# Synchronous_Rectification_Stage.net
KiCad netlist of a schematic drawn in Altium Designer
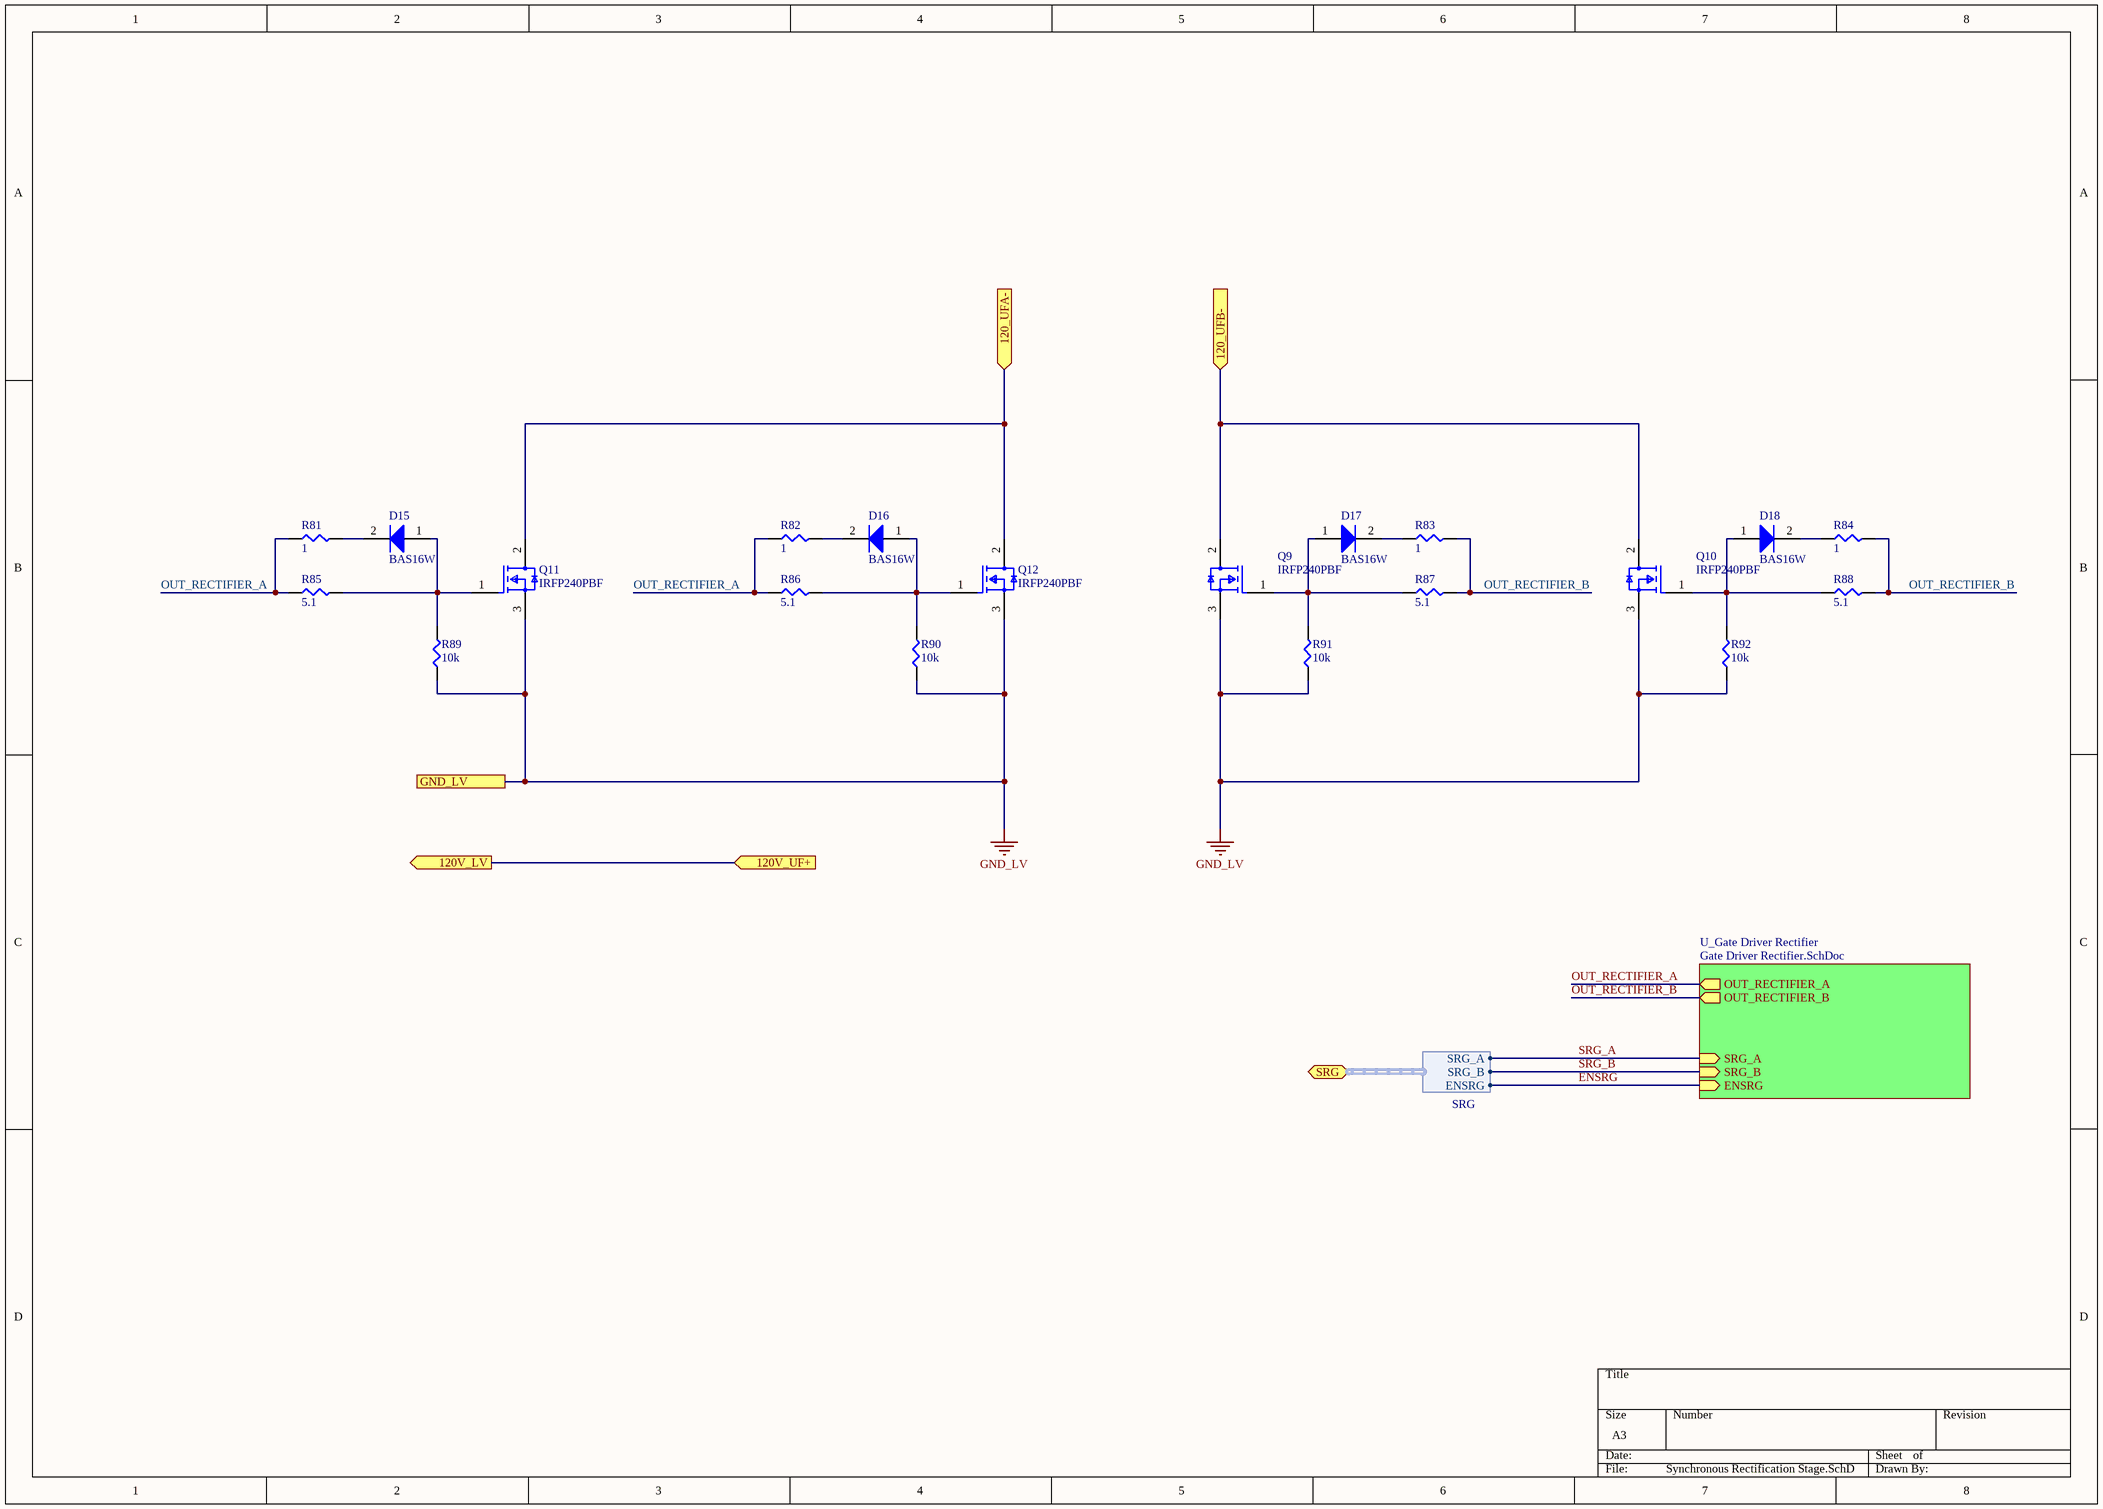
[diagram p0: Synchronous Rectification Stage.SchDoc]

(export (version "E")
  (design (tool "Eeschema 10.0.6"))
  (components
    (comp (ref "D15")
      (value "BAS16W")
      (footprint "SODFL250X110-2N")
      (description "Silicon Switching Diode, SOT323, Reel, Green")
      (fields (field (name "MANUFACTURER") "Infineon"))
      (libsource (lib "PFC_Stage") (part "BAS16_SOD"))
    )
    (comp (ref "D16")
      (value "BAS16W")
      (footprint "SODFL250X110-2N")
      (description "Silicon Switching Diode, SOT323, Reel, Green")
      (fields (field (name "MANUFACTURER") "Infineon"))
      (libsource (lib "PFC_Stage") (part "BAS16_SOD"))
    )
    (comp (ref "D17")
      (value "BAS16W")
      (footprint "SODFL250X110-2N")
      (description "Silicon Switching Diode, SOT323, Reel, Green")
      (fields (field (name "MANUFACTURER") "Infineon"))
      (libsource (lib "PFC_Stage") (part "BAS16_SOD"))
    )
    (comp (ref "D18")
      (value "BAS16W")
      (footprint "SODFL250X110-2N")
      (description "Silicon Switching Diode, SOT323, Reel, Green")
      (fields (field (name "MANUFACTURER") "Infineon"))
      (libsource (lib "PFC_Stage") (part "BAS16_SOD"))
    )
    (comp (ref "Q9")
      (value "IRFP240PBF")
      (footprint "FP-E19-0614-MFG")
      (description "MOSFET N-CH 200V 20A TO-247AC")
      (fields
        (field (name "MANUFACTURER") "Vishay")
        (field (name "OCTOPART") "https://octopart.com/irfp240pbf-vishay-46527395")
      )
      (libsource (lib "Altium Content Vault") (part "277670f45256a45703965f138927d09"))
    )
    (comp (ref "Q10")
      (value "IRFP240PBF")
      (footprint "FP-E19-0614-MFG")
      (description "MOSFET N-CH 200V 20A TO-247AC")
      (fields
        (field (name "MANUFACTURER") "Vishay")
        (field (name "OCTOPART") "https://octopart.com/irfp240pbf-vishay-46527395")
      )
      (libsource (lib "Altium Content Vault") (part "277670f45256a45703965f138927d09"))
    )
    (comp (ref "Q11")
      (value "IRFP240PBF")
      (footprint "FP-E19-0614-MFG")
      (description "MOSFET N-CH 200V 20A TO-247AC")
      (fields
        (field (name "MANUFACTURER") "Vishay")
        (field (name "OCTOPART") "https://octopart.com/irfp240pbf-vishay-46527395")
      )
      (libsource (lib "Altium Content Vault") (part "277670f45256a45703965f138927d09"))
    )
    (comp (ref "Q12")
      (value "IRFP240PBF")
      (footprint "FP-E19-0614-MFG")
      (description "MOSFET N-CH 200V 20A TO-247AC")
      (fields
        (field (name "MANUFACTURER") "Vishay")
        (field (name "OCTOPART") "https://octopart.com/irfp240pbf-vishay-46527395")
      )
      (libsource (lib "Altium Content Vault") (part "277670f45256a45703965f138927d09"))
    )
    (comp (ref "R81")
      (value "1")
      (footprint "SMD-0805-RES")
      (description "RES SMD 1 OHM 1% 1/3W 0805")
      (fields (field (name "PART NUMBER") "ERJ-6BQF1R0V") (field (name "DIGI-KEY PART NUMBER") "P17499CT-ND"))
      (libsource (lib "Panasonic_ERJ_0805") (part "ERJ-6BQF1R0V"))
    )
    (comp (ref "R82")
      (value "1")
      (footprint "SMD-0805-RES")
      (description "RES SMD 1 OHM 1% 1/3W 0805")
      (fields (field (name "PART NUMBER") "ERJ-6BQF1R0V") (field (name "DIGI-KEY PART NUMBER") "P17499CT-ND"))
      (libsource (lib "Panasonic_ERJ_0805") (part "ERJ-6BQF1R0V"))
    )
    (comp (ref "R83")
      (value "1")
      (footprint "SMD-0805-RES")
      (description "RES SMD 1 OHM 1% 1/3W 0805")
      (fields (field (name "PART NUMBER") "ERJ-6BQF1R0V") (field (name "DIGI-KEY PART NUMBER") "P17499CT-ND"))
      (libsource (lib "Panasonic_ERJ_0805") (part "ERJ-6BQF1R0V"))
    )
    (comp (ref "R84")
      (value "1")
      (footprint "SMD-0805-RES")
      (description "RES SMD 1 OHM 1% 1/3W 0805")
      (fields (field (name "PART NUMBER") "ERJ-6BQF1R0V") (field (name "DIGI-KEY PART NUMBER") "P17499CT-ND"))
      (libsource (lib "Panasonic_ERJ_0805") (part "ERJ-6BQF1R0V"))
    )
    (comp (ref "R85")
      (value "5.1")
      (footprint "SMD-1206-RES")
      (description "RES SMD 5.1 OHM 1% 1/2W 1206")
      (fields (field (name "PART NUMBER") "ERJ-8BQF5R1V") (field (name "DIGI-KEY PART NUMBER") "P17617CT-ND"))
      (libsource (lib "Panasonic_ERJ_1206") (part "ERJ-8BQF5R1V"))
    )
    (comp (ref "R86")
      (value "5.1")
      (footprint "SMD-1206-RES")
      (description "RES SMD 5.1 OHM 1% 1/2W 1206")
      (fields (field (name "PART NUMBER") "ERJ-8BQF5R1V") (field (name "DIGI-KEY PART NUMBER") "P17617CT-ND"))
      (libsource (lib "Panasonic_ERJ_1206") (part "ERJ-8BQF5R1V"))
    )
    (comp (ref "R87")
      (value "5.1")
      (footprint "SMD-1206-RES")
      (description "RES SMD 5.1 OHM 1% 1/2W 1206")
      (fields (field (name "PART NUMBER") "ERJ-8BQF5R1V") (field (name "DIGI-KEY PART NUMBER") "P17617CT-ND"))
      (libsource (lib "Panasonic_ERJ_1206") (part "ERJ-8BQF5R1V"))
    )
    (comp (ref "R88")
      (value "5.1")
      (footprint "SMD-1206-RES")
      (description "RES SMD 5.1 OHM 1% 1/2W 1206")
      (fields (field (name "PART NUMBER") "ERJ-8BQF5R1V") (field (name "DIGI-KEY PART NUMBER") "P17617CT-ND"))
      (libsource (lib "Panasonic_ERJ_1206") (part "ERJ-8BQF5R1V"))
    )
    (comp (ref "R89")
      (value "10k")
      (footprint "SMD-1206-RES")
      (description "RES SMD 10K OHM 1% 1/4W 1206")
      (fields
        (field (name "PART NUMBER") "ERJ-8ENF1002V")
        (field (name "DIGI-KEY PART NUMBER") "P10.0KFCT-ND")
      )
      (libsource (lib "Panasonic_ERJ_1206") (part "ERJ-8ENF1002V"))
    )
    (comp (ref "R90")
      (value "10k")
      (footprint "SMD-1206-RES")
      (description "RES SMD 10K OHM 1% 1/4W 1206")
      (fields
        (field (name "PART NUMBER") "ERJ-8ENF1002V")
        (field (name "DIGI-KEY PART NUMBER") "P10.0KFCT-ND")
      )
      (libsource (lib "Panasonic_ERJ_1206") (part "ERJ-8ENF1002V"))
    )
    (comp (ref "R91")
      (value "10k")
      (footprint "SMD-1206-RES")
      (description "RES SMD 10K OHM 1% 1/4W 1206")
      (fields
        (field (name "PART NUMBER") "ERJ-8ENF1002V")
        (field (name "DIGI-KEY PART NUMBER") "P10.0KFCT-ND")
      )
      (libsource (lib "Panasonic_ERJ_1206") (part "ERJ-8ENF1002V"))
    )
    (comp (ref "R92")
      (value "10k")
      (footprint "SMD-1206-RES")
      (description "RES SMD 10K OHM 1% 1/4W 1206")
      (fields
        (field (name "PART NUMBER") "ERJ-8ENF1002V")
        (field (name "DIGI-KEY PART NUMBER") "P10.0KFCT-ND")
      )
      (libsource (lib "Panasonic_ERJ_1206") (part "ERJ-8ENF1002V"))
    )
  )
  (nets
    (net (code "3") (name "/120_UFA-") (class "Default")
      (node (ref "Q11") (pin "2") (pinfunction "D_2") (pintype "passive"))
      (node (ref "Q12") (pin "2") (pinfunction "D_2") (pintype "passive"))
    )
    (net (code "4") (name "/120_UFB-") (class "Default")
      (node (ref "Q10") (pin "2") (pinfunction "D_2") (pintype "passive"))
      (node (ref "Q9") (pin "2") (pinfunction "D_2") (pintype "passive"))
    )
    (net (code "6") (name "/OUT_RECTIFIER_A") (class "Default")
      (node (ref "R81") (pin "1") (pinfunction "1_1") (pintype "passive"))
      (node (ref "R82") (pin "1") (pinfunction "1_1") (pintype "passive"))
      (node (ref "R85") (pin "1") (pinfunction "1_1") (pintype "passive"))
      (node (ref "R86") (pin "1") (pinfunction "1_1") (pintype "passive"))
    )
    (net (code "7") (name "/OUT_RECTIFIER_B") (class "Default")
      (node (ref "R83") (pin "2") (pinfunction "2_2") (pintype "passive"))
      (node (ref "R84") (pin "2") (pinfunction "2_2") (pintype "passive"))
      (node (ref "R87") (pin "2") (pinfunction "2_2") (pintype "passive"))
      (node (ref "R88") (pin "2") (pinfunction "2_2") (pintype "passive"))
    )
    (net (code "11") (name "GND_LV") (class "Default")
      (node (ref "Q10") (pin "3") (pinfunction "S_3") (pintype "passive"))
      (node (ref "Q11") (pin "3") (pinfunction "S_3") (pintype "passive"))
      (node (ref "Q12") (pin "3") (pinfunction "S_3") (pintype "passive"))
      (node (ref "Q9") (pin "3") (pinfunction "S_3") (pintype "passive"))
      (node (ref "R89") (pin "1") (pinfunction "1_1") (pintype "passive"))
      (node (ref "R90") (pin "1") (pinfunction "1_1") (pintype "passive"))
      (node (ref "R91") (pin "1") (pinfunction "1_1") (pintype "passive"))
      (node (ref "R92") (pin "1") (pinfunction "1_1") (pintype "passive"))
    )
    (net (code "12") (name "Net-(D15-A)") (class "Default")
      (node (ref "D15") (pin "1") (pinfunction "A_1") (pintype "passive"))
      (node (ref "Q11") (pin "1") (pinfunction "G_1") (pintype "passive"))
      (node (ref "R85") (pin "2") (pinfunction "2_2") (pintype "passive"))
      (node (ref "R89") (pin "2") (pinfunction "2_2") (pintype "passive"))
    )
    (net (code "13") (name "Net-(D15-K)") (class "Default")
      (node (ref "D15") (pin "2") (pinfunction "K_2") (pintype "passive"))
      (node (ref "R81") (pin "2") (pinfunction "2_2") (pintype "passive"))
    )
    (net (code "14") (name "Net-(D16-A)") (class "Default")
      (node (ref "D16") (pin "1") (pinfunction "A_1") (pintype "passive"))
      (node (ref "Q12") (pin "1") (pinfunction "G_1") (pintype "passive"))
      (node (ref "R86") (pin "2") (pinfunction "2_2") (pintype "passive"))
      (node (ref "R90") (pin "2") (pinfunction "2_2") (pintype "passive"))
    )
    (net (code "15") (name "Net-(D16-K)") (class "Default")
      (node (ref "D16") (pin "2") (pinfunction "K_2") (pintype "passive"))
      (node (ref "R82") (pin "2") (pinfunction "2_2") (pintype "passive"))
    )
    (net (code "16") (name "Net-(D17-A)") (class "Default")
      (node (ref "D17") (pin "1") (pinfunction "A_1") (pintype "passive"))
      (node (ref "Q9") (pin "1") (pinfunction "G_1") (pintype "passive"))
      (node (ref "R87") (pin "1") (pinfunction "1_1") (pintype "passive"))
      (node (ref "R91") (pin "2") (pinfunction "2_2") (pintype "passive"))
    )
    (net (code "17") (name "Net-(D17-K)") (class "Default")
      (node (ref "D17") (pin "2") (pinfunction "K_2") (pintype "passive"))
      (node (ref "R83") (pin "1") (pinfunction "1_1") (pintype "passive"))
    )
    (net (code "18") (name "Net-(D18-A)") (class "Default")
      (node (ref "D18") (pin "1") (pinfunction "A_1") (pintype "passive"))
      (node (ref "Q10") (pin "1") (pinfunction "G_1") (pintype "passive"))
      (node (ref "R88") (pin "1") (pinfunction "1_1") (pintype "passive"))
      (node (ref "R92") (pin "2") (pinfunction "2_2") (pintype "passive"))
    )
    (net (code "19") (name "Net-(D18-K)") (class "Default")
      (node (ref "D18") (pin "2") (pinfunction "K_2") (pintype "passive"))
      (node (ref "R84") (pin "1") (pinfunction "1_1") (pintype "passive"))
    )
  )
)
